# buttons.net
KiCad netlist of a schematic drawn in Altium Designer
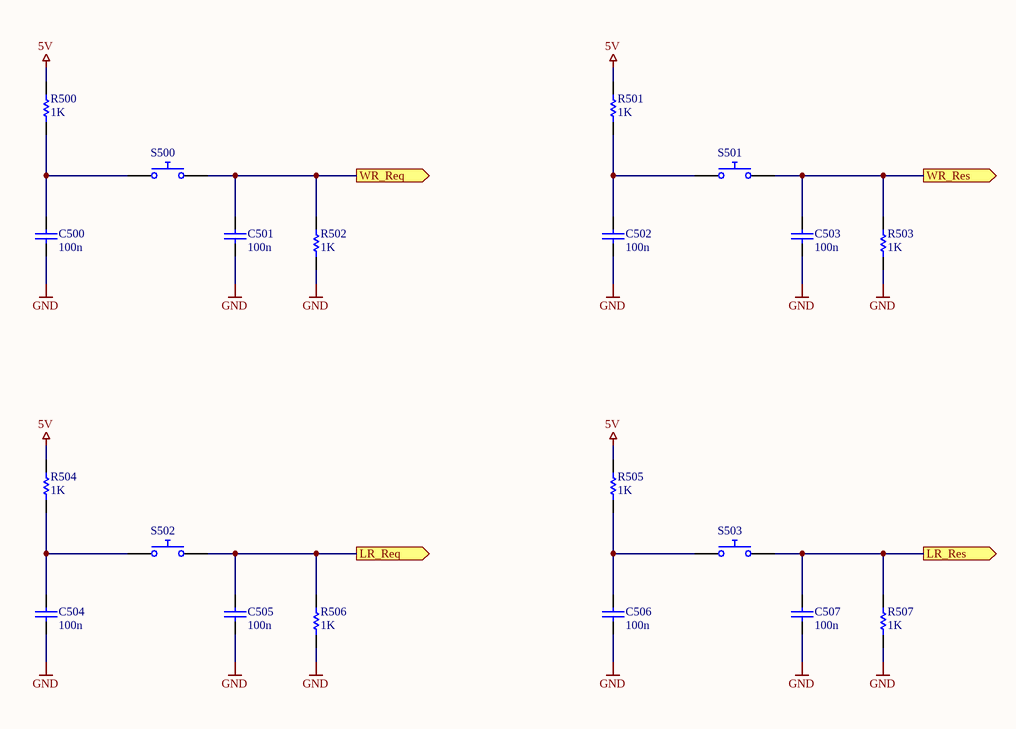
[diagram p0: buttons.SchDoc]

(export (version "E")
  (design (tool "Eeschema 10.0.6"))
  (components
    (comp (ref "C500")
      (value "100n")
      (description "Capacitor")
      (libsource (lib "Simulation Generic Components") (part "Capacitor"))
    )
    (comp (ref "C501")
      (value "100n")
      (description "Capacitor")
      (libsource (lib "Simulation Generic Components") (part "Capacitor"))
    )
    (comp (ref "C502")
      (value "100n")
      (description "Capacitor")
      (libsource (lib "Simulation Generic Components") (part "Capacitor"))
    )
    (comp (ref "C503")
      (value "100n")
      (description "Capacitor")
      (libsource (lib "Simulation Generic Components") (part "Capacitor"))
    )
    (comp (ref "C504")
      (value "100n")
      (description "Capacitor")
      (libsource (lib "Simulation Generic Components") (part "Capacitor"))
    )
    (comp (ref "C505")
      (value "100n")
      (description "Capacitor")
      (libsource (lib "Simulation Generic Components") (part "Capacitor"))
    )
    (comp (ref "C506")
      (value "100n")
      (description "Capacitor")
      (libsource (lib "Simulation Generic Components") (part "Capacitor"))
    )
    (comp (ref "C507")
      (value "100n")
      (description "Capacitor")
      (libsource (lib "Simulation Generic Components") (part "Capacitor"))
    )
    (comp (ref "R500")
      (value "1K")
      (description "Resistor")
      (libsource (lib "Simulation Generic Components") (part "Resistor"))
    )
    (comp (ref "R501")
      (value "1K")
      (description "Resistor")
      (libsource (lib "Simulation Generic Components") (part "Resistor"))
    )
    (comp (ref "R502")
      (value "1K")
      (description "Resistor")
      (libsource (lib "Simulation Generic Components") (part "Resistor"))
    )
    (comp (ref "R503")
      (value "1K")
      (description "Resistor")
      (libsource (lib "Simulation Generic Components") (part "Resistor"))
    )
    (comp (ref "R504")
      (value "1K")
      (description "Resistor")
      (libsource (lib "Simulation Generic Components") (part "Resistor"))
    )
    (comp (ref "R505")
      (value "1K")
      (description "Resistor")
      (libsource (lib "Simulation Generic Components") (part "Resistor"))
    )
    (comp (ref "R506")
      (value "1K")
      (description "Resistor")
      (libsource (lib "Simulation Generic Components") (part "Resistor"))
    )
    (comp (ref "R507")
      (value "1K")
      (description "Resistor")
      (libsource (lib "Simulation Generic Components") (part "Resistor"))
    )
    (comp (ref "S500")
      (value "Push Button Normally Opened")
      (libsource (lib "Simulation Generic Components") (part "Push Button NO"))
    )
    (comp (ref "S501")
      (value "Push Button Normally Opened")
      (libsource (lib "Simulation Generic Components") (part "Push Button NO"))
    )
    (comp (ref "S502")
      (value "Push Button Normally Opened")
      (libsource (lib "Simulation Generic Components") (part "Push Button NO"))
    )
    (comp (ref "S503")
      (value "Push Button Normally Opened")
      (libsource (lib "Simulation Generic Components") (part "Push Button NO"))
    )
  )
  (nets
    (net (code "1") (name "/LR_Req") (class "Default")
      (node (ref "C505") (pin "2") (pinfunction "2_2") (pintype "passive"))
      (node (ref "R506") (pin "2") (pinfunction "2_2") (pintype "passive"))
      (node (ref "S502") (pin "2") (pinfunction "2_2") (pintype "passive"))
    )
    (net (code "2") (name "/LR_Res") (class "Default")
      (node (ref "C507") (pin "2") (pinfunction "2_2") (pintype "passive"))
      (node (ref "R507") (pin "2") (pinfunction "2_2") (pintype "passive"))
      (node (ref "S503") (pin "2") (pinfunction "2_2") (pintype "passive"))
    )
    (net (code "3") (name "/WR_Req") (class "Default")
      (node (ref "C501") (pin "2") (pinfunction "2_2") (pintype "passive"))
      (node (ref "R502") (pin "2") (pinfunction "2_2") (pintype "passive"))
      (node (ref "S500") (pin "2") (pinfunction "2_2") (pintype "passive"))
    )
    (net (code "4") (name "/WR_Res") (class "Default")
      (node (ref "C503") (pin "2") (pinfunction "2_2") (pintype "passive"))
      (node (ref "R503") (pin "2") (pinfunction "2_2") (pintype "passive"))
      (node (ref "S501") (pin "2") (pinfunction "2_2") (pintype "passive"))
    )
    (net (code "5") (name "5V") (class "Default")
      (node (ref "R500") (pin "2") (pinfunction "2_2") (pintype "passive"))
      (node (ref "R501") (pin "2") (pinfunction "2_2") (pintype "passive"))
      (node (ref "R504") (pin "2") (pinfunction "2_2") (pintype "passive"))
      (node (ref "R505") (pin "2") (pinfunction "2_2") (pintype "passive"))
    )
    (net (code "6") (name "GND") (class "Default")
      (node (ref "C500") (pin "1") (pinfunction "1_1") (pintype "passive"))
      (node (ref "C501") (pin "1") (pinfunction "1_1") (pintype "passive"))
      (node (ref "C502") (pin "1") (pinfunction "1_1") (pintype "passive"))
      (node (ref "C503") (pin "1") (pinfunction "1_1") (pintype "passive"))
      (node (ref "C504") (pin "1") (pinfunction "1_1") (pintype "passive"))
      (node (ref "C505") (pin "1") (pinfunction "1_1") (pintype "passive"))
      (node (ref "C506") (pin "1") (pinfunction "1_1") (pintype "passive"))
      (node (ref "C507") (pin "1") (pinfunction "1_1") (pintype "passive"))
      (node (ref "R502") (pin "1") (pinfunction "1_1") (pintype "passive"))
      (node (ref "R503") (pin "1") (pinfunction "1_1") (pintype "passive"))
      (node (ref "R506") (pin "1") (pinfunction "1_1") (pintype "passive"))
      (node (ref "R507") (pin "1") (pinfunction "1_1") (pintype "passive"))
    )
    (net (code "7") (name "Net-(C500-Pad2)") (class "Default")
      (node (ref "C500") (pin "2") (pinfunction "2_2") (pintype "passive"))
      (node (ref "R500") (pin "1") (pinfunction "1_1") (pintype "passive"))
      (node (ref "S500") (pin "1") (pinfunction "1_1") (pintype "passive"))
    )
    (net (code "8") (name "Net-(C502-Pad2)") (class "Default")
      (node (ref "C502") (pin "2") (pinfunction "2_2") (pintype "passive"))
      (node (ref "R501") (pin "1") (pinfunction "1_1") (pintype "passive"))
      (node (ref "S501") (pin "1") (pinfunction "1_1") (pintype "passive"))
    )
    (net (code "9") (name "Net-(C504-Pad2)") (class "Default")
      (node (ref "C504") (pin "2") (pinfunction "2_2") (pintype "passive"))
      (node (ref "R504") (pin "1") (pinfunction "1_1") (pintype "passive"))
      (node (ref "S502") (pin "1") (pinfunction "1_1") (pintype "passive"))
    )
    (net (code "10") (name "Net-(C506-Pad2)") (class "Default")
      (node (ref "C506") (pin "2") (pinfunction "2_2") (pintype "passive"))
      (node (ref "R505") (pin "1") (pinfunction "1_1") (pintype "passive"))
      (node (ref "S503") (pin "1") (pinfunction "1_1") (pintype "passive"))
    )
  )
)
